# uUSB_breakout_v1.net
KiCad netlist of a schematic drawn in EAGLE
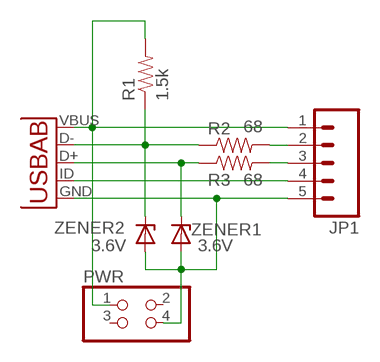
[diagram p0: schematic, sheet 1]

(export (version "E")
  (design (tool "Eeschema 10.0.6"))
  (components
    (comp (ref "JP1")
      (value "M05PTH")
      (footprint "eagle-import:1X05")
      (libsource (lib "eagle-import") (part "M05PTH"))
    )
    (comp (ref "PWR")
      (value "PINHD-2X2")
      (footprint "eagle-import:2X02")
      (libsource (lib "eagle-import") (part "PINHD-2X2"))
    )
    (comp (ref "R1")
      (value "1.5k")
      (footprint "eagle-import:0805")
      (libsource (lib "eagle-import") (part "RESISTOR0805-RES"))
    )
    (comp (ref "R2")
      (value "68")
      (footprint "eagle-import:0805")
      (libsource (lib "eagle-import") (part "RESISTOR0805-RES"))
    )
    (comp (ref "R3")
      (value "68")
      (footprint "eagle-import:0805")
      (libsource (lib "eagle-import") (part "RESISTOR0805-RES"))
    )
    (comp (ref "UUSB")
      (value "USB-AB")
      (footprint "eagle-import:USB-AB-MICRO-SMD")
      (libsource (lib "eagle-import") (part "USB-AB"))
    )
    (comp (ref "ZENER1")
      (value "3.6V")
      (footprint "eagle-import:SOD80C")
      (libsource (lib "eagle-import") (part "ZENER-DIODESOD80C"))
    )
    (comp (ref "ZENER2")
      (value "3.6V")
      (footprint "eagle-import:SOD80C")
      (libsource (lib "eagle-import") (part "ZENER-DIODESOD80C"))
    )
  )
  (nets
    (net (code "1") (name "Net-(JP1-Pad1)") (class "Default")
      (node (ref "JP1") (pin "1") (pinfunction "1_1") (pintype "passive"))
      (node (ref "PWR") (pin "1") (pinfunction "1_1") (pintype "passive"))
      (node (ref "R1") (pin "2") (pinfunction "2_2") (pintype "passive"))
      (node (ref "UUSB") (pin "VBUS") (pinfunction "VBUS_VBUS") (pintype "bidirectional"))
    )
    (net (code "2") (name "Net-(JP1-Pad2)") (class "Default")
      (node (ref "JP1") (pin "2") (pinfunction "2_2") (pintype "passive"))
      (node (ref "R2") (pin "2") (pinfunction "2_2") (pintype "passive"))
    )
    (net (code "3") (name "Net-(JP1-Pad3)") (class "Default")
      (node (ref "JP1") (pin "3") (pinfunction "3_3") (pintype "passive"))
      (node (ref "R3") (pin "2") (pinfunction "2_2") (pintype "passive"))
    )
    (net (code "4") (name "Net-(JP1-Pad5)") (class "Default")
      (node (ref "JP1") (pin "5") (pinfunction "5_5") (pintype "passive"))
      (node (ref "PWR") (pin "4") (pinfunction "4_4") (pintype "passive"))
      (node (ref "UUSB") (pin "GND") (pinfunction "GND_GND") (pintype "bidirectional"))
      (node (ref "ZENER1") (pin "A") (pinfunction "A_A") (pintype "passive"))
      (node (ref "ZENER2") (pin "A") (pinfunction "A_A") (pintype "passive"))
    )
    (net (code "5") (name "Net-(R1-Pad1)") (class "Default")
      (node (ref "R1") (pin "1") (pinfunction "1_1") (pintype "passive"))
      (node (ref "R2") (pin "1") (pinfunction "1_1") (pintype "passive"))
      (node (ref "UUSB") (pin "D-") (pinfunction "D-_D-") (pintype "bidirectional"))
      (node (ref "ZENER2") (pin "C") (pinfunction "C_C") (pintype "passive"))
    )
    (net (code "6") (name "Net-(R3-Pad1)") (class "Default")
      (node (ref "R3") (pin "1") (pinfunction "1_1") (pintype "passive"))
      (node (ref "UUSB") (pin "D+") (pinfunction "D+_D+") (pintype "bidirectional"))
      (node (ref "ZENER1") (pin "C") (pinfunction "C_C") (pintype "passive"))
    )
    (net (code "7") (name "Net-(UUSB-USBID)") (class "Default")
      (node (ref "JP1") (pin "4") (pinfunction "4_4") (pintype "passive"))
      (node (ref "UUSB") (pin "ID") (pinfunction "USBID_ID") (pintype "bidirectional"))
    )
    (net (code "8") (name "unconnected-(PWR-Pad2)") (class "Default")
      (node (ref "PWR") (pin "2") (pinfunction "2_2") (pintype "passive"))
    )
    (net (code "9") (name "unconnected-(PWR-Pad3)") (class "Default")
      (node (ref "PWR") (pin "3") (pinfunction "3_3") (pintype "passive"))
    )
  )
)
